# g030f6.net
KiCad netlist of a schematic drawn in EAGLE
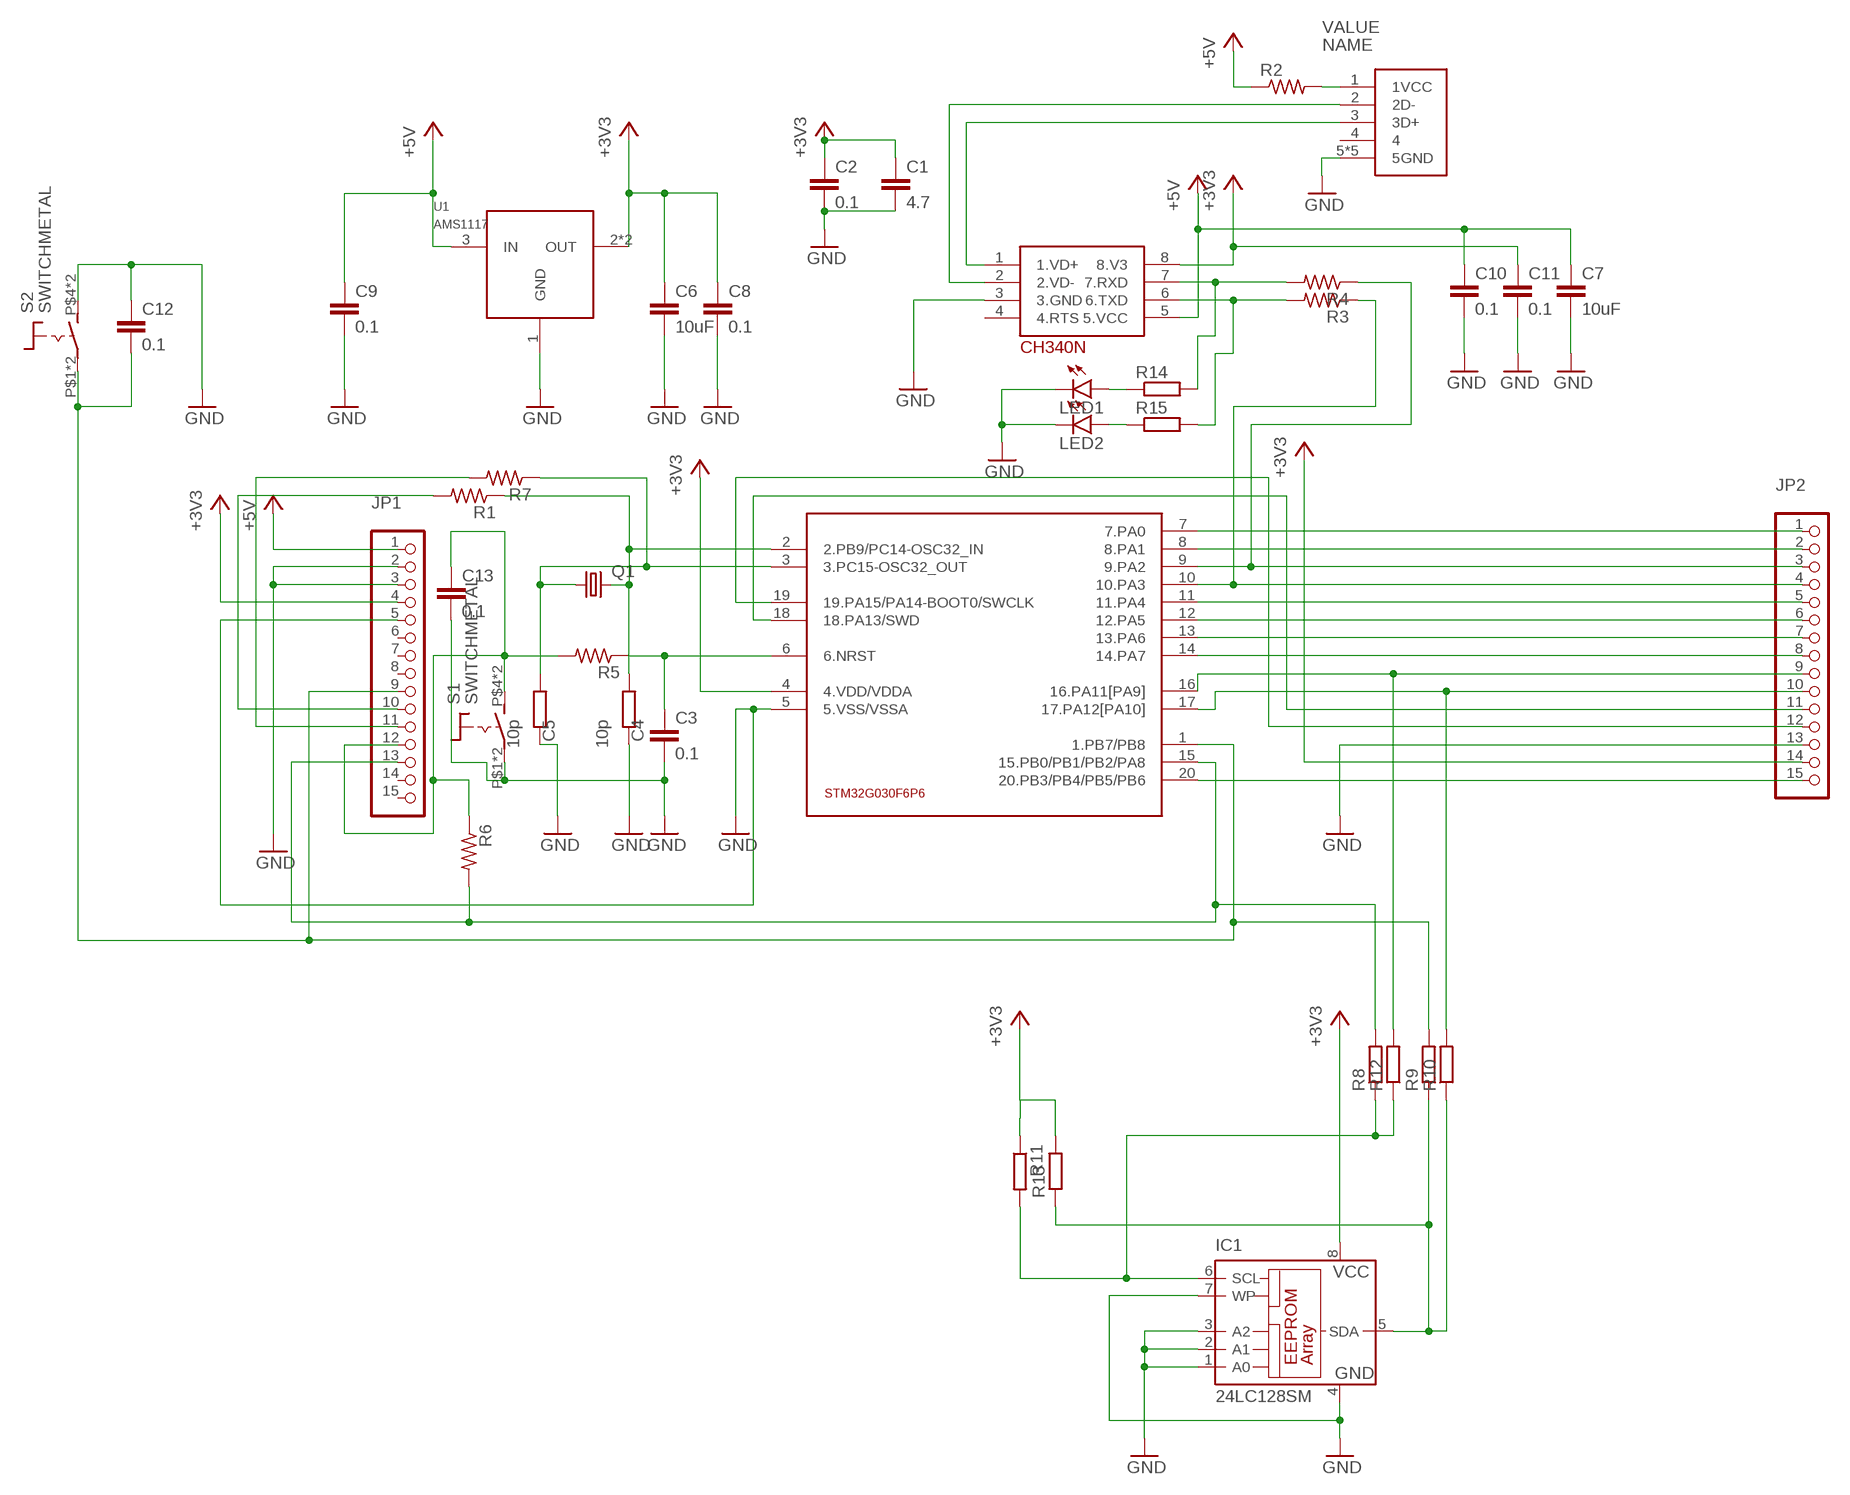
[diagram p0: schematic, sheet 1]

(export (version "E")
  (design (tool "Eeschema 10.0.6"))
  (components
    (comp (ref "C1")
      (value "4.7")
      (footprint "eagle-import:C0805")
      (libsource (lib "eagle-import") (part "C-EUC0805"))
    )
    (comp (ref "C2")
      (value "0.1")
      (footprint "eagle-import:C0402")
      (libsource (lib "eagle-import") (part "C-EUC0402"))
    )
    (comp (ref "C3")
      (value "0.1")
      (footprint "eagle-import:C0402")
      (libsource (lib "eagle-import") (part "C-EUC0402"))
    )
    (comp (ref "C4")
      (value "10p")
      (footprint "eagle-import:R0402")
      (libsource (lib "eagle-import") (part "R-EU_R0402"))
    )
    (comp (ref "C5")
      (value "10p")
      (footprint "eagle-import:R0402")
      (libsource (lib "eagle-import") (part "R-EU_R0402"))
    )
    (comp (ref "C6")
      (value "10uF")
      (footprint "eagle-import:C0805")
      (libsource (lib "eagle-import") (part "C-EUC0805"))
    )
    (comp (ref "C7")
      (value "10uF")
      (footprint "eagle-import:C0805")
      (libsource (lib "eagle-import") (part "C-EUC0805"))
    )
    (comp (ref "C8")
      (value "0.1")
      (footprint "eagle-import:C0402")
      (libsource (lib "eagle-import") (part "C-EUC0402"))
    )
    (comp (ref "C9")
      (value "0.1")
      (footprint "eagle-import:C0402")
      (libsource (lib "eagle-import") (part "C-EUC0402"))
    )
    (comp (ref "C10")
      (value "0.1")
      (footprint "eagle-import:C0402")
      (libsource (lib "eagle-import") (part "C-EUC0402"))
    )
    (comp (ref "C11")
      (value "0.1")
      (footprint "eagle-import:C0402")
      (libsource (lib "eagle-import") (part "C-EUC0402"))
    )
    (comp (ref "C12")
      (value "0.1")
      (footprint "eagle-import:C0402")
      (libsource (lib "eagle-import") (part "C-EUC0402"))
    )
    (comp (ref "C13")
      (value "0.1")
      (footprint "eagle-import:C0402")
      (libsource (lib "eagle-import") (part "C-EUC0402"))
    )
    (comp (ref "CONN1")
      (value "MICROUSB")
      (footprint "eagle-import:MICROUSB5")
      (libsource (lib "eagle-import") (part "MICROUSB"))
    )
    (comp (ref "IC1")
      (value "24LC128SM")
      (footprint "eagle-import:SO-08M")
      (fields (field (name "MF") "MICROCHIP") (field (name "MPN") "24LC128-I/SM"))
      (libsource (lib "eagle-import") (part "24SMLC128"))
    )
    (comp (ref "JP1")
      (value "PINHD-1X15")
      (footprint "eagle-import:1X15")
      (libsource (lib "eagle-import") (part "PINHD-1X15"))
    )
    (comp (ref "JP2")
      (value "PINHD-1X15")
      (footprint "eagle-import:1X15")
      (libsource (lib "eagle-import") (part "PINHD-1X15"))
    )
    (comp (ref "LED1")
      (value "LEDSML0603")
      (footprint "eagle-import:SML0603")
      (libsource (lib "eagle-import") (part "LEDSML0603"))
    )
    (comp (ref "LED2")
      (value "LEDSML0603")
      (footprint "eagle-import:SML0603")
      (libsource (lib "eagle-import") (part "LEDSML0603"))
    )
    (comp (ref "Q1")
      (value "CRYSTALTC26V")
      (footprint "eagle-import:TC26V")
      (libsource (lib "eagle-import") (part "CRYSTALTC26V"))
    )
    (comp (ref "R1")
      (value "R-US_R0402")
      (footprint "eagle-import:R0402")
      (libsource (lib "eagle-import") (part "R-US_R0402"))
    )
    (comp (ref "R2")
      (value "R-US_R2010")
      (footprint "eagle-import:R2010")
      (libsource (lib "eagle-import") (part "R-US_R2010"))
    )
    (comp (ref "R3")
      (value "R-US_R0402")
      (footprint "eagle-import:R0402")
      (libsource (lib "eagle-import") (part "R-US_R0402"))
    )
    (comp (ref "R4")
      (value "R-US_R0402")
      (footprint "eagle-import:R0402")
      (libsource (lib "eagle-import") (part "R-US_R0402"))
    )
    (comp (ref "R5")
      (value "R-US_R0402")
      (footprint "eagle-import:R0402")
      (libsource (lib "eagle-import") (part "R-US_R0402"))
    )
    (comp (ref "R6")
      (value "R-US_R0402")
      (footprint "eagle-import:R0402")
      (libsource (lib "eagle-import") (part "R-US_R0402"))
    )
    (comp (ref "R7")
      (value "R-US_R0402")
      (footprint "eagle-import:R0402")
      (libsource (lib "eagle-import") (part "R-US_R0402"))
    )
    (comp (ref "R8")
      (value "R-EU_R0603")
      (footprint "eagle-import:R0603")
      (libsource (lib "eagle-import") (part "R-EU_R0603"))
    )
    (comp (ref "R9")
      (value "R-EU_R0603")
      (footprint "eagle-import:R0603")
      (libsource (lib "eagle-import") (part "R-EU_R0603"))
    )
    (comp (ref "R10")
      (value "R-EU_R0603")
      (footprint "eagle-import:R0603")
      (libsource (lib "eagle-import") (part "R-EU_R0603"))
    )
    (comp (ref "R11")
      (value "R-EU_R0603")
      (footprint "eagle-import:R0603")
      (libsource (lib "eagle-import") (part "R-EU_R0603"))
    )
    (comp (ref "R12")
      (value "R-EU_R0603")
      (footprint "eagle-import:R0603")
      (libsource (lib "eagle-import") (part "R-EU_R0603"))
    )
    (comp (ref "R13")
      (value "R-EU_R0603")
      (footprint "eagle-import:R0603")
      (libsource (lib "eagle-import") (part "R-EU_R0603"))
    )
    (comp (ref "R14")
      (value "R-EU_R0402")
      (footprint "eagle-import:R0402")
      (libsource (lib "eagle-import") (part "R-EU_R0402"))
    )
    (comp (ref "R15")
      (value "R-EU_R0402")
      (footprint "eagle-import:R0402")
      (libsource (lib "eagle-import") (part "R-EU_R0402"))
    )
    (comp (ref "S1")
      (value "SWITCHMETAL")
      (footprint "eagle-import:SWMET")
      (libsource (lib "eagle-import") (part "SWITCHMETAL"))
    )
    (comp (ref "S2")
      (value "SWITCHMETAL")
      (footprint "eagle-import:SWMET")
      (libsource (lib "eagle-import") (part "SWITCHMETAL"))
    )
    (comp (ref "U$1")
      (value "STM32GO3OF6P6")
      (footprint "eagle-import:TSSOP20")
      (libsource (lib "eagle-import") (part "STM32GO3OF6P6"))
    )
    (comp (ref "U$3")
      (value "CH340N")
      (footprint "eagle-import:SO-8")
      (libsource (lib "eagle-import") (part "CH340N"))
    )
    (comp (ref "U1")
      (value "AMS1117")
      (footprint "eagle-import:SOT223")
      (libsource (lib "eagle-import") (part "AMS1117"))
    )
  )
  (nets
    (net (code "1") (name "+3V3") (class "Default")
      (node (ref "C1") (pin "1") (pinfunction "1_1") (pintype "passive"))
      (node (ref "C11") (pin "1") (pinfunction "1_1") (pintype "passive"))
      (node (ref "C2") (pin "1") (pinfunction "1_1") (pintype "passive"))
      (node (ref "C6") (pin "1") (pinfunction "1_1") (pintype "passive"))
      (node (ref "C8") (pin "1") (pinfunction "1_1") (pintype "passive"))
      (node (ref "IC1") (pin "8") (pinfunction "VCC_8") (pintype "power_in"))
      (node (ref "JP1") (pin "4") (pinfunction "4_4") (pintype "passive"))
      (node (ref "JP2") (pin "14") (pinfunction "14_14") (pintype "passive"))
      (node (ref "R11") (pin "1") (pinfunction "1_1") (pintype "passive"))
      (node (ref "R13") (pin "2") (pinfunction "2_2") (pintype "passive"))
      (node (ref "U$1") (pin "4") (pinfunction "4.VDD/VDDA_4") (pintype "power_in"))
      (node (ref "U$3") (pin "8") (pinfunction "8.V3_8") (pintype "bidirectional"))
      (node (ref "U1") (pin "2") (pinfunction "OUT_2") (pintype "power_in"))
      (node (ref "U1") (pin "4") (pinfunction "OUT_4") (pintype "power_in"))
    )
    (net (code "2") (name "+5V") (class "Default")
      (node (ref "C10") (pin "1") (pinfunction "1_1") (pintype "passive"))
      (node (ref "C7") (pin "1") (pinfunction "1_1") (pintype "passive"))
      (node (ref "C9") (pin "1") (pinfunction "1_1") (pintype "passive"))
      (node (ref "JP1") (pin "1") (pinfunction "1_1") (pintype "passive"))
      (node (ref "R2") (pin "1") (pinfunction "1_1") (pintype "passive"))
      (node (ref "U$3") (pin "5") (pinfunction "5.VCC_5") (pintype "bidirectional"))
      (node (ref "U1") (pin "3") (pinfunction "IN_3") (pintype "power_in"))
    )
    (net (code "3") (name "GND") (class "Default")
      (node (ref "C1") (pin "2") (pinfunction "2_2") (pintype "passive"))
      (node (ref "C10") (pin "2") (pinfunction "2_2") (pintype "passive"))
      (node (ref "C11") (pin "2") (pinfunction "2_2") (pintype "passive"))
      (node (ref "C12") (pin "1") (pinfunction "1_1") (pintype "passive"))
      (node (ref "C13") (pin "2") (pinfunction "2_2") (pintype "passive"))
      (node (ref "C2") (pin "2") (pinfunction "2_2") (pintype "passive"))
      (node (ref "C3") (pin "2") (pinfunction "2_2") (pintype "passive"))
      (node (ref "C4") (pin "2") (pinfunction "2_2") (pintype "passive"))
      (node (ref "C5") (pin "2") (pinfunction "2_2") (pintype "passive"))
      (node (ref "C6") (pin "2") (pinfunction "2_2") (pintype "passive"))
      (node (ref "C7") (pin "2") (pinfunction "2_2") (pintype "passive"))
      (node (ref "C8") (pin "2") (pinfunction "2_2") (pintype "passive"))
      (node (ref "C9") (pin "2") (pinfunction "2_2") (pintype "passive"))
      (node (ref "CONN1") (pin "5") (pinfunction "5GND_5") (pintype "bidirectional"))
      (node (ref "CONN1") (pin "P$1") (pinfunction "5GND_P$1") (pintype "bidirectional"))
      (node (ref "CONN1") (pin "P$2") (pinfunction "5GND_P$2") (pintype "bidirectional"))
      (node (ref "CONN1") (pin "P$6") (pinfunction "5GND_P$6") (pintype "bidirectional"))
      (node (ref "CONN1") (pin "P$7") (pinfunction "5GND_P$7") (pintype "bidirectional"))
      (node (ref "IC1") (pin "1") (pinfunction "A0_1") (pintype "input"))
      (node (ref "IC1") (pin "2") (pinfunction "A1_2") (pintype "input"))
      (node (ref "IC1") (pin "3") (pinfunction "A2_3") (pintype "input"))
      (node (ref "IC1") (pin "4") (pinfunction "GND_4") (pintype "power_in"))
      (node (ref "IC1") (pin "7") (pinfunction "WP_7") (pintype "input"))
      (node (ref "JP1") (pin "2") (pinfunction "2_2") (pintype "passive"))
      (node (ref "JP1") (pin "3") (pinfunction "3_3") (pintype "passive"))
      (node (ref "JP1") (pin "5") (pinfunction "5_5") (pintype "passive"))
      (node (ref "JP2") (pin "13") (pinfunction "13_13") (pintype "passive"))
      (node (ref "LED1") (pin "C") (pinfunction "C_C") (pintype "passive"))
      (node (ref "LED2") (pin "C") (pinfunction "C_C") (pintype "passive"))
      (node (ref "S1") (pin "P$1") (pinfunction "P_P$1") (pintype "passive"))
      (node (ref "S1") (pin "P$1@1") (pinfunction "P_P$1@1") (pintype "passive"))
      (node (ref "S2") (pin "P$4") (pinfunction "S_P$4") (pintype "passive"))
      (node (ref "S2") (pin "P$4@1") (pinfunction "S_P$4@1") (pintype "passive"))
      (node (ref "U$1") (pin "5") (pinfunction "5.VSS/VSSA_5") (pintype "power_in"))
      (node (ref "U$3") (pin "3") (pinfunction "3.GND_3") (pintype "bidirectional"))
      (node (ref "U1") (pin "1") (pinfunction "GND_1") (pintype "bidirectional"))
    )
    (net (code "4") (name "Net-(C13-Pad1)") (class "Default")
      (node (ref "C13") (pin "1") (pinfunction "1_1") (pintype "passive"))
      (node (ref "JP1") (pin "12") (pinfunction "12_12") (pintype "passive"))
      (node (ref "R5") (pin "2") (pinfunction "2_2") (pintype "passive"))
      (node (ref "R6") (pin "1") (pinfunction "1_1") (pintype "passive"))
      (node (ref "S1") (pin "P$4") (pinfunction "S_P$4") (pintype "passive"))
      (node (ref "S1") (pin "P$4@1") (pinfunction "S_P$4@1") (pintype "passive"))
    )
    (net (code "5") (name "Net-(CONN1-1VCC)") (class "Default")
      (node (ref "CONN1") (pin "1") (pinfunction "1VCC_1") (pintype "bidirectional"))
      (node (ref "R2") (pin "2") (pinfunction "2_2") (pintype "passive"))
    )
    (net (code "6") (name "Net-(CONN1-2D-)") (class "Default")
      (node (ref "CONN1") (pin "2") (pinfunction "2D-_2") (pintype "bidirectional"))
      (node (ref "U$3") (pin "2") (pinfunction "2.VD-_2") (pintype "bidirectional"))
    )
    (net (code "7") (name "Net-(CONN1-3D+)") (class "Default")
      (node (ref "CONN1") (pin "3") (pinfunction "3D+_3") (pintype "bidirectional"))
      (node (ref "U$3") (pin "1") (pinfunction "1.VD+_1") (pintype "bidirectional"))
    )
    (net (code "8") (name "Net-(IC1-SCL)") (class "Default")
      (node (ref "IC1") (pin "6") (pinfunction "SCL_6") (pintype "input"))
      (node (ref "R11") (pin "2") (pinfunction "2_2") (pintype "passive"))
      (node (ref "R12") (pin "1") (pinfunction "1_1") (pintype "passive"))
      (node (ref "R8") (pin "1") (pinfunction "1_1") (pintype "passive"))
    )
    (net (code "9") (name "Net-(IC1-SDA)") (class "Default")
      (node (ref "IC1") (pin "5") (pinfunction "SDA_5") (pintype "bidirectional"))
      (node (ref "R10") (pin "1") (pinfunction "1_1") (pintype "passive"))
      (node (ref "R13") (pin "1") (pinfunction "1_1") (pintype "passive"))
      (node (ref "R9") (pin "1") (pinfunction "1_1") (pintype "passive"))
    )
    (net (code "10") (name "Net-(JP1-Pad10)") (class "Default")
      (node (ref "JP1") (pin "10") (pinfunction "10_10") (pintype "passive"))
      (node (ref "R1") (pin "2") (pinfunction "2_2") (pintype "passive"))
    )
    (net (code "11") (name "Net-(JP1-Pad11)") (class "Default")
      (node (ref "JP1") (pin "11") (pinfunction "11_11") (pintype "passive"))
      (node (ref "R7") (pin "2") (pinfunction "2_2") (pintype "passive"))
    )
    (net (code "12") (name "Net-(LED1-PadA)") (class "Default")
      (node (ref "LED1") (pin "A") (pinfunction "A_A") (pintype "passive"))
      (node (ref "R14") (pin "1") (pinfunction "1_1") (pintype "passive"))
    )
    (net (code "13") (name "Net-(LED2-PadA)") (class "Default")
      (node (ref "LED2") (pin "A") (pinfunction "A_A") (pintype "passive"))
      (node (ref "R15") (pin "1") (pinfunction "1_1") (pintype "passive"))
    )
    (net (code "14") (name "Net-(U$1-1.PB7{slash}PB8)") (class "Default")
      (node (ref "C12") (pin "2") (pinfunction "2_2") (pintype "passive"))
      (node (ref "JP1") (pin "9") (pinfunction "9_9") (pintype "passive"))
      (node (ref "R9") (pin "2") (pinfunction "2_2") (pintype "passive"))
      (node (ref "S2") (pin "P$1") (pinfunction "P_P$1") (pintype "passive"))
      (node (ref "S2") (pin "P$1@1") (pinfunction "P_P$1@1") (pintype "passive"))
      (node (ref "U$1") (pin "1") (pinfunction "1.PB7/PB8_1") (pintype "bidirectional"))
    )
    (net (code "15") (name "Net-(U$1-2.PB9{slash}PC14-OSC32_IN)") (class "Default")
      (node (ref "C4") (pin "1") (pinfunction "1_1") (pintype "passive"))
      (node (ref "Q1") (pin "2") (pinfunction "2_2") (pintype "passive"))
      (node (ref "R1") (pin "1") (pinfunction "1_1") (pintype "passive"))
      (node (ref "U$1") (pin "2") (pinfunction "2.PB9/PC14-OSC32_IN_2") (pintype "bidirectional"))
    )
    (net (code "16") (name "Net-(U$1-3.PC15-OSC32_OUT)") (class "Default")
      (node (ref "C5") (pin "1") (pinfunction "1_1") (pintype "passive"))
      (node (ref "Q1") (pin "1") (pinfunction "1_1") (pintype "passive"))
      (node (ref "R7") (pin "1") (pinfunction "1_1") (pintype "passive"))
      (node (ref "U$1") (pin "3") (pinfunction "3.PC15-OSC32_OUT_3") (pintype "bidirectional"))
    )
    (net (code "17") (name "Net-(U$1-6.NRST)") (class "Default")
      (node (ref "C3") (pin "1") (pinfunction "1_1") (pintype "passive"))
      (node (ref "R5") (pin "1") (pinfunction "1_1") (pintype "passive"))
      (node (ref "U$1") (pin "6") (pinfunction "6.NRST_6") (pintype "input"))
    )
    (net (code "18") (name "Net-(U$1-7.PA0)") (class "Default")
      (node (ref "JP2") (pin "1") (pinfunction "1_1") (pintype "passive"))
      (node (ref "U$1") (pin "7") (pinfunction "7.PA0_7") (pintype "bidirectional"))
    )
    (net (code "19") (name "Net-(U$1-8.PA1)") (class "Default")
      (node (ref "JP2") (pin "2") (pinfunction "2_2") (pintype "passive"))
      (node (ref "U$1") (pin "8") (pinfunction "8.PA1_8") (pintype "bidirectional"))
    )
    (net (code "20") (name "Net-(U$1-9.PA2)") (class "Default")
      (node (ref "JP2") (pin "3") (pinfunction "3_3") (pintype "passive"))
      (node (ref "R4") (pin "1") (pinfunction "1_1") (pintype "passive"))
      (node (ref "U$1") (pin "9") (pinfunction "9.PA2_9") (pintype "bidirectional"))
    )
    (net (code "21") (name "Net-(U$1-10.PA3)") (class "Default")
      (node (ref "JP2") (pin "4") (pinfunction "4_4") (pintype "passive"))
      (node (ref "R3") (pin "1") (pinfunction "1_1") (pintype "passive"))
      (node (ref "U$1") (pin "10") (pinfunction "10.PA3_10") (pintype "bidirectional"))
    )
    (net (code "22") (name "Net-(U$1-11.PA4)") (class "Default")
      (node (ref "JP2") (pin "5") (pinfunction "5_5") (pintype "passive"))
      (node (ref "U$1") (pin "11") (pinfunction "11.PA4_11") (pintype "bidirectional"))
    )
    (net (code "23") (name "Net-(U$1-12.PA5)") (class "Default")
      (node (ref "JP2") (pin "6") (pinfunction "6_6") (pintype "passive"))
      (node (ref "U$1") (pin "12") (pinfunction "12.PA5_12") (pintype "bidirectional"))
    )
    (net (code "24") (name "Net-(U$1-13.PA6)") (class "Default")
      (node (ref "JP2") (pin "7") (pinfunction "7_7") (pintype "passive"))
      (node (ref "U$1") (pin "13") (pinfunction "13.PA6_13") (pintype "bidirectional"))
    )
    (net (code "25") (name "Net-(U$1-14.PA7)") (class "Default")
      (node (ref "JP2") (pin "8") (pinfunction "8_8") (pintype "passive"))
      (node (ref "U$1") (pin "14") (pinfunction "14.PA7_14") (pintype "bidirectional"))
    )
    (net (code "26") (name "Net-(U$1-15.PB0{slash}PB1{slash}PB2{slash}PA8)") (class "Default")
      (node (ref "JP1") (pin "13") (pinfunction "13_13") (pintype "passive"))
      (node (ref "R6") (pin "2") (pinfunction "2_2") (pintype "passive"))
      (node (ref "R8") (pin "2") (pinfunction "2_2") (pintype "passive"))
      (node (ref "U$1") (pin "15") (pinfunction "15.PB0/PB1/PB2/PA8_15") (pintype "bidirectional"))
    )
    (net (code "27") (name "Net-(U$1-16.PA11[PA9])") (class "Default")
      (node (ref "JP2") (pin "9") (pinfunction "9_9") (pintype "passive"))
      (node (ref "R12") (pin "2") (pinfunction "2_2") (pintype "passive"))
      (node (ref "U$1") (pin "16") (pinfunction "16.PA11[PA9]_16") (pintype "bidirectional"))
    )
    (net (code "28") (name "Net-(U$1-17.PA12[PA10])") (class "Default")
      (node (ref "JP2") (pin "10") (pinfunction "10_10") (pintype "passive"))
      (node (ref "R10") (pin "2") (pinfunction "2_2") (pintype "passive"))
      (node (ref "U$1") (pin "17") (pinfunction "17.PA12[PA10]_17") (pintype "bidirectional"))
    )
    (net (code "29") (name "Net-(U$1-18.PA13{slash}SWD)") (class "Default")
      (node (ref "JP2") (pin "11") (pinfunction "11_11") (pintype "passive"))
      (node (ref "U$1") (pin "18") (pinfunction "18.PA13/SWD_18") (pintype "bidirectional"))
    )
    (net (code "30") (name "Net-(U$1-19.PA15{slash}PA14-BOOT0{slash}SWCLK)") (class "Default")
      (node (ref "JP2") (pin "12") (pinfunction "12_12") (pintype "passive"))
      (node (ref "U$1") (pin "19") (pinfunction "19.PA15/PA14-BOOT0/SWCLK_19") (pintype "bidirectional"))
    )
    (net (code "31") (name "Net-(U$1-20.PB3{slash}PB4{slash}PB5{slash}PB6)") (class "Default")
      (node (ref "JP2") (pin "15") (pinfunction "15_15") (pintype "passive"))
      (node (ref "U$1") (pin "20") (pinfunction "20.PB3/PB4/PB5/PB6_20") (pintype "bidirectional"))
    )
    (net (code "32") (name "Net-(U$3-6.TXD)") (class "Default")
      (node (ref "R15") (pin "2") (pinfunction "2_2") (pintype "passive"))
      (node (ref "R3") (pin "2") (pinfunction "2_2") (pintype "passive"))
      (node (ref "U$3") (pin "6") (pinfunction "6.TXD_6") (pintype "bidirectional"))
    )
    (net (code "33") (name "Net-(U$3-7.RXD)") (class "Default")
      (node (ref "R14") (pin "2") (pinfunction "2_2") (pintype "passive"))
      (node (ref "R4") (pin "2") (pinfunction "2_2") (pintype "passive"))
      (node (ref "U$3") (pin "7") (pinfunction "7.RXD_7") (pintype "bidirectional"))
    )
    (net (code "34") (name "unconnected-(CONN1-Pad4)") (class "Default")
      (node (ref "CONN1") (pin "4") (pinfunction "4_4") (pintype "bidirectional"))
    )
    (net (code "35") (name "unconnected-(JP1-Pad6)") (class "Default")
      (node (ref "JP1") (pin "6") (pinfunction "6_6") (pintype "passive"))
    )
    (net (code "36") (name "unconnected-(JP1-Pad7)") (class "Default")
      (node (ref "JP1") (pin "7") (pinfunction "7_7") (pintype "passive"))
    )
    (net (code "37") (name "unconnected-(JP1-Pad8)") (class "Default")
      (node (ref "JP1") (pin "8") (pinfunction "8_8") (pintype "passive"))
    )
    (net (code "38") (name "unconnected-(JP1-Pad14)") (class "Default")
      (node (ref "JP1") (pin "14") (pinfunction "14_14") (pintype "passive"))
    )
    (net (code "39") (name "unconnected-(JP1-Pad15)") (class "Default")
      (node (ref "JP1") (pin "15") (pinfunction "15_15") (pintype "passive"))
    )
    (net (code "40") (name "unconnected-(U$3-4.RTS-Pad4)") (class "Default")
      (node (ref "U$3") (pin "4") (pinfunction "4.RTS_4") (pintype "bidirectional"))
    )
  )
)
